# Pithy_Screen.net
KiCad netlist of a schematic drawn in EAGLE
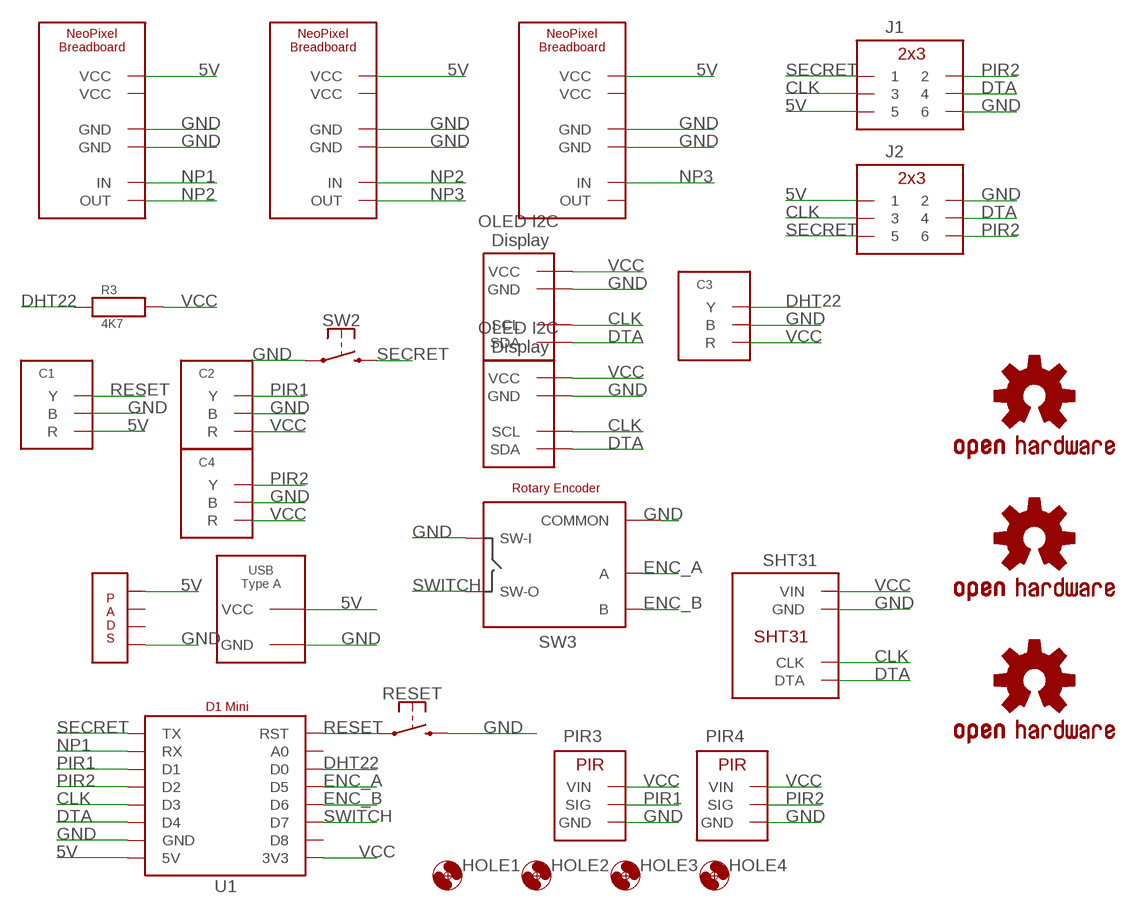
[diagram p0: schematic, sheet 1]

(export (version "E")
  (design (tool "Eeschema 10.0.6"))
  (components
    (comp (ref "C1")
      (value "JST_2MM_3PIN")
      (footprint "eagle-import:JST_2MM_3PIN")
      (libsource (lib "eagle-import") (part "JST_2MM_3PIN"))
    )
    (comp (ref "C2")
      (value "JST_2MM_3PIN")
      (footprint "eagle-import:JST_2MM_3PIN")
      (libsource (lib "eagle-import") (part "JST_2MM_3PIN"))
    )
    (comp (ref "C3")
      (value "JST_2MM_3PIN")
      (footprint "eagle-import:JST_2MM_3PIN")
      (libsource (lib "eagle-import") (part "JST_2MM_3PIN"))
    )
    (comp (ref "C4")
      (value "JST_2MM_3PIN")
      (footprint "eagle-import:JST_2MM_3PIN")
      (libsource (lib "eagle-import") (part "JST_2MM_3PIN"))
    )
    (comp (ref "HOLE1")
      (value "HOLE_3.2")
      (footprint "eagle-import:HOLE_3.2")
      (libsource (lib "eagle-import") (part "HOLE_3.2"))
    )
    (comp (ref "HOLE2")
      (value "HOLE_3.2")
      (footprint "eagle-import:HOLE_3.2")
      (libsource (lib "eagle-import") (part "HOLE_3.2"))
    )
    (comp (ref "HOLE3")
      (value "HOLE_3.2")
      (footprint "eagle-import:HOLE_3.2")
      (libsource (lib "eagle-import") (part "HOLE_3.2"))
    )
    (comp (ref "HOLE4")
      (value "HOLE_3.2")
      (footprint "eagle-import:HOLE_3.2")
      (libsource (lib "eagle-import") (part "HOLE_3.2"))
    )
    (comp (ref "J1")
      (value "DIL_2X03FEMALE")
      (footprint "eagle-import:2X3-RAF")
      (libsource (lib "eagle-import") (part "DIL_2X03FEMALE"))
    )
    (comp (ref "J2")
      (value "DIL_2X03FEMALE")
      (footprint "eagle-import:2X3-RAF")
      (libsource (lib "eagle-import") (part "DIL_2X03FEMALE"))
    )
    (comp (ref "LOGO1")
      (value "OSHW-LOGOL")
      (footprint "eagle-import:OSHW-LOGO-L")
      (libsource (lib "eagle-import") (part "OSHW-LOGOL"))
    )
    (comp (ref "LOGO2")
      (value "OSHW-LOGOM")
      (footprint "eagle-import:OSHW-LOGO-M")
      (libsource (lib "eagle-import") (part "OSHW-LOGOM"))
    )
    (comp (ref "LOGO3")
      (value "OSHW-LOGOS")
      (footprint "eagle-import:OSHW-LOGO-S")
      (libsource (lib "eagle-import") (part "OSHW-LOGOS"))
    )
    (comp (ref "NP1")
      (value "NEOPIXEL_BREADBOARD")
      (footprint "eagle-import:NEOPIXEL_BREADBOARD")
      (libsource (lib "eagle-import") (part "NEOPIXEL_BREADBOARD"))
    )
    (comp (ref "NP2")
      (value "NEOPIXEL_BREADBOARD")
      (footprint "eagle-import:NEOPIXEL_BREADBOARD")
      (libsource (lib "eagle-import") (part "NEOPIXEL_BREADBOARD"))
    )
    (comp (ref "NP3")
      (value "NEOPIXEL_BREADBOARD")
      (footprint "eagle-import:NEOPIXEL_BREADBOARD")
      (libsource (lib "eagle-import") (part "NEOPIXEL_BREADBOARD"))
    )
    (comp (ref "PIR3")
      (value "PIR45DEG")
      (footprint "eagle-import:PIR_45DEG")
      (libsource (lib "eagle-import") (part "PIR45DEG"))
    )
    (comp (ref "PIR4")
      (value "PIR45DEG")
      (footprint "eagle-import:PIR_45DEG")
      (libsource (lib "eagle-import") (part "PIR45DEG"))
    )
    (comp (ref "R3")
      (value "4K7")
      (footprint "eagle-import:1_4W_RESISTOR")
      (libsource (lib "eagle-import") (part "1/4W_RESISTOR"))
    )
    (comp (ref "RESET")
      (value "SPDT_MOMENTARY")
      (footprint "eagle-import:SPDT_RIGHT_ANGLE")
      (libsource (lib "eagle-import") (part "SPDT_MOMENTARY"))
    )
    (comp (ref "SHT31")
      (value "SHT31RIGHT_ANGLED")
      (footprint "eagle-import:SHT31_RIGHT_ANGLE")
      (libsource (lib "eagle-import") (part "SHT31RIGHT_ANGLED"))
    )
    (comp (ref "SW2")
      (value "SPDT_MOMENTARY")
      (footprint "eagle-import:SPDT_RIGHT_ANGLE")
      (libsource (lib "eagle-import") (part "SPDT_MOMENTARY"))
    )
    (comp (ref "SW3")
      (value "ENCODER")
      (footprint "eagle-import:ROTARY_ENCODER")
      (libsource (lib "eagle-import") (part "ROTARY_ENCODER"))
    )
    (comp (ref "U$1")
      (value "USB_TYPE_A")
      (footprint "eagle-import:USB_TYPE_A_BACKWARDS")
      (libsource (lib "eagle-import") (part "USB_TYPE_A"))
    )
    (comp (ref "U$2")
      (value "PADS_4")
      (footprint "eagle-import:PADS_4")
      (libsource (lib "eagle-import") (part "PADS_4"))
    )
    (comp (ref "U1")
      (value "D1_MINI")
      (footprint "eagle-import:D1_MINI")
      (libsource (lib "eagle-import") (part "D1_MINI"))
    )
    (comp (ref "U2")
      (value "OLED_I2C_0.9\"VCC_LEFT")
      (footprint "eagle-import:OLED_I2C_0.9__ALT")
      (libsource (lib "eagle-import") (part "OLED_I2C_0.9{dblquote}VCC_LEFT"))
    )
    (comp (ref "U3")
      (value "OLED_I2C_0.9\"VCC_LEFT")
      (footprint "eagle-import:OLED_I2C_0.9__ALT")
      (libsource (lib "eagle-import") (part "OLED_I2C_0.9{dblquote}VCC_LEFT"))
    )
  )
  (nets
    (net (code "1") (name "/5V") (class "Default")
      (node (ref "C1") (pin "RED") (pinfunction "R_RED") (pintype "bidirectional"))
      (node (ref "J1") (pin "5") (pinfunction "5_5") (pintype "bidirectional"))
      (node (ref "J2") (pin "1") (pinfunction "1_1") (pintype "bidirectional"))
      (node (ref "NP1") (pin "VCC") (pinfunction "VCC_VCC") (pintype "bidirectional"))
      (node (ref "NP2") (pin "VCC") (pinfunction "VCC_VCC") (pintype "bidirectional"))
      (node (ref "NP3") (pin "VCC") (pinfunction "VCC_VCC") (pintype "bidirectional"))
      (node (ref "U$1") (pin "VCC") (pinfunction "VCC_VCC") (pintype "bidirectional"))
      (node (ref "U$2") (pin "P$4") (pinfunction "P$4_P$4") (pintype "bidirectional"))
      (node (ref "U1") (pin "5V") (pinfunction "5V_5V") (pintype "bidirectional"))
    )
    (net (code "2") (name "/CLK") (class "Default")
      (node (ref "J1") (pin "3") (pinfunction "3_3") (pintype "bidirectional"))
      (node (ref "J2") (pin "3") (pinfunction "3_3") (pintype "bidirectional"))
      (node (ref "SHT31") (pin "CLK") (pinfunction "CLK_CLK") (pintype "bidirectional"))
      (node (ref "U1") (pin "D3") (pinfunction "D3_D3") (pintype "bidirectional"))
      (node (ref "U2") (pin "SCL") (pinfunction "SCL_SCL") (pintype "bidirectional"))
      (node (ref "U3") (pin "SCL") (pinfunction "SCL_SCL") (pintype "bidirectional"))
    )
    (net (code "3") (name "/DHT22") (class "Default")
      (node (ref "C3") (pin "YELLOW") (pinfunction "Y_YELLOW") (pintype "bidirectional"))
      (node (ref "R3") (pin "P$1") (pinfunction "P$1_P$1") (pintype "passive"))
      (node (ref "U1") (pin "D0") (pinfunction "D0_D0") (pintype "bidirectional"))
    )
    (net (code "4") (name "/DTA") (class "Default")
      (node (ref "J1") (pin "4") (pinfunction "4_4") (pintype "bidirectional"))
      (node (ref "J2") (pin "4") (pinfunction "4_4") (pintype "bidirectional"))
      (node (ref "SHT31") (pin "DTA") (pinfunction "DTA_DTA") (pintype "bidirectional"))
      (node (ref "U1") (pin "D4") (pinfunction "D4_D4") (pintype "bidirectional"))
      (node (ref "U2") (pin "SDA") (pinfunction "SDA_SDA") (pintype "bidirectional"))
      (node (ref "U3") (pin "SDA") (pinfunction "SDA_SDA") (pintype "bidirectional"))
    )
    (net (code "5") (name "/ENC_A") (class "Default")
      (node (ref "SW3") (pin "A") (pinfunction "A_A") (pintype "output"))
      (node (ref "U1") (pin "D5") (pinfunction "D5_D5") (pintype "bidirectional"))
    )
    (net (code "6") (name "/ENC_B") (class "Default")
      (node (ref "SW3") (pin "B") (pinfunction "B_B") (pintype "output"))
      (node (ref "U1") (pin "D6") (pinfunction "D6_D6") (pintype "bidirectional"))
    )
    (net (code "7") (name "/GND") (class "Default")
      (node (ref "C1") (pin "BLACK") (pinfunction "B_BLACK") (pintype "bidirectional"))
      (node (ref "C2") (pin "BLACK") (pinfunction "B_BLACK") (pintype "bidirectional"))
      (node (ref "C3") (pin "BLACK") (pinfunction "B_BLACK") (pintype "bidirectional"))
      (node (ref "C4") (pin "BLACK") (pinfunction "B_BLACK") (pintype "bidirectional"))
      (node (ref "J1") (pin "6") (pinfunction "6_6") (pintype "bidirectional"))
      (node (ref "J2") (pin "2") (pinfunction "2_2") (pintype "bidirectional"))
      (node (ref "NP1") (pin "GND") (pinfunction "GND_GND") (pintype "bidirectional"))
      (node (ref "NP1") (pin "GND@2") (pinfunction "GND_GND@2") (pintype "bidirectional"))
      (node (ref "NP2") (pin "GND") (pinfunction "GND_GND") (pintype "bidirectional"))
      (node (ref "NP2") (pin "GND@2") (pinfunction "GND_GND@2") (pintype "bidirectional"))
      (node (ref "NP3") (pin "GND") (pinfunction "GND_GND") (pintype "bidirectional"))
      (node (ref "NP3") (pin "GND@2") (pinfunction "GND_GND@2") (pintype "bidirectional"))
      (node (ref "PIR3") (pin "GND") (pinfunction "GND_GND") (pintype "bidirectional"))
      (node (ref "PIR4") (pin "GND") (pinfunction "GND_GND") (pintype "bidirectional"))
      (node (ref "RESET") (pin "2") (pinfunction "3_2") (pintype "passive"))
      (node (ref "SHT31") (pin "GND") (pinfunction "GND_GND") (pintype "bidirectional"))
      (node (ref "SW2") (pin "1") (pinfunction "1_1") (pintype "passive"))
      (node (ref "SW3") (pin "C") (pinfunction "COMMON_C") (pintype "input"))
      (node (ref "SW3") (pin "SW+") (pinfunction "SW-I_SW+") (pintype "input"))
      (node (ref "U$1") (pin "GND") (pinfunction "GND_GND") (pintype "bidirectional"))
      (node (ref "U$2") (pin "P$1") (pinfunction "P$1_P$1") (pintype "bidirectional"))
      (node (ref "U1") (pin "GND") (pinfunction "GND_GND") (pintype "bidirectional"))
      (node (ref "U2") (pin "GND") (pinfunction "GND_GND") (pintype "power_in"))
      (node (ref "U3") (pin "GND") (pinfunction "GND_GND") (pintype "power_in"))
    )
    (net (code "8") (name "/NP1") (class "Default")
      (node (ref "NP1") (pin "IN") (pinfunction "IN_IN") (pintype "bidirectional"))
      (node (ref "U1") (pin "RX") (pinfunction "RX_RX") (pintype "bidirectional"))
    )
    (net (code "9") (name "/NP2") (class "Default")
      (node (ref "NP1") (pin "OUT") (pinfunction "OUT_OUT") (pintype "bidirectional"))
      (node (ref "NP2") (pin "IN") (pinfunction "IN_IN") (pintype "bidirectional"))
    )
    (net (code "10") (name "/NP3") (class "Default")
      (node (ref "NP2") (pin "OUT") (pinfunction "OUT_OUT") (pintype "bidirectional"))
      (node (ref "NP3") (pin "IN") (pinfunction "IN_IN") (pintype "bidirectional"))
    )
    (net (code "11") (name "/PIR1") (class "Default")
      (node (ref "C2") (pin "YELLOW") (pinfunction "Y_YELLOW") (pintype "bidirectional"))
      (node (ref "PIR3") (pin "SIG") (pinfunction "SIG_SIG") (pintype "bidirectional"))
      (node (ref "U1") (pin "D1") (pinfunction "D1_D1") (pintype "bidirectional"))
    )
    (net (code "12") (name "/PIR2") (class "Default")
      (node (ref "C4") (pin "YELLOW") (pinfunction "Y_YELLOW") (pintype "bidirectional"))
      (node (ref "J1") (pin "2") (pinfunction "2_2") (pintype "bidirectional"))
      (node (ref "J2") (pin "6") (pinfunction "6_6") (pintype "bidirectional"))
      (node (ref "PIR4") (pin "SIG") (pinfunction "SIG_SIG") (pintype "bidirectional"))
      (node (ref "U1") (pin "D2") (pinfunction "D2_D2") (pintype "bidirectional"))
    )
    (net (code "13") (name "/RESET") (class "Default")
      (node (ref "C1") (pin "YELLOW") (pinfunction "Y_YELLOW") (pintype "bidirectional"))
      (node (ref "RESET") (pin "1") (pinfunction "1_1") (pintype "passive"))
      (node (ref "U1") (pin "RST") (pinfunction "RST_RST") (pintype "bidirectional"))
    )
    (net (code "14") (name "/SECRET") (class "Default")
      (node (ref "J1") (pin "1") (pinfunction "1_1") (pintype "bidirectional"))
      (node (ref "J2") (pin "5") (pinfunction "5_5") (pintype "bidirectional"))
      (node (ref "SW2") (pin "2") (pinfunction "3_2") (pintype "passive"))
      (node (ref "U1") (pin "TX") (pinfunction "TX_TX") (pintype "bidirectional"))
    )
    (net (code "15") (name "/SWITCH") (class "Default")
      (node (ref "SW3") (pin "SW-") (pinfunction "SW-O_SW-") (pintype "output"))
      (node (ref "U1") (pin "D7") (pinfunction "D7_D7") (pintype "bidirectional"))
    )
    (net (code "16") (name "/VCC") (class "Default")
      (node (ref "C2") (pin "RED") (pinfunction "R_RED") (pintype "bidirectional"))
      (node (ref "C3") (pin "RED") (pinfunction "R_RED") (pintype "bidirectional"))
      (node (ref "C4") (pin "RED") (pinfunction "R_RED") (pintype "bidirectional"))
      (node (ref "PIR3") (pin "VCC") (pinfunction "VIN_VCC") (pintype "bidirectional"))
      (node (ref "PIR4") (pin "VCC") (pinfunction "VIN_VCC") (pintype "bidirectional"))
      (node (ref "R3") (pin "P$2") (pinfunction "P$2_P$2") (pintype "passive"))
      (node (ref "SHT31") (pin "VIN") (pinfunction "VIN_VIN") (pintype "bidirectional"))
      (node (ref "U1") (pin "3V3") (pinfunction "3V3_3V3") (pintype "bidirectional"))
      (node (ref "U2") (pin "VCC") (pinfunction "VCC_VCC") (pintype "power_in"))
      (node (ref "U3") (pin "VCC") (pinfunction "VCC_VCC") (pintype "power_in"))
    )
    (net (code "17") (name "unconnected-(NP1-VCC-PadVCC@2)") (class "Default")
      (node (ref "NP1") (pin "VCC@2") (pinfunction "VCC_VCC@2") (pintype "bidirectional"))
    )
    (net (code "18") (name "unconnected-(NP2-VCC-PadVCC@2)") (class "Default")
      (node (ref "NP2") (pin "VCC@2") (pinfunction "VCC_VCC@2") (pintype "bidirectional"))
    )
    (net (code "19") (name "unconnected-(NP3-PadOUT)") (class "Default")
      (node (ref "NP3") (pin "OUT") (pinfunction "OUT_OUT") (pintype "bidirectional"))
    )
    (net (code "20") (name "unconnected-(NP3-VCC-PadVCC@2)") (class "Default")
      (node (ref "NP3") (pin "VCC@2") (pinfunction "VCC_VCC@2") (pintype "bidirectional"))
    )
    (net (code "21") (name "unconnected-(U$2-PadP$2)") (class "Default")
      (node (ref "U$2") (pin "P$2") (pinfunction "P$2_P$2") (pintype "bidirectional"))
    )
    (net (code "22") (name "unconnected-(U$2-PadP$3)") (class "Default")
      (node (ref "U$2") (pin "P$3") (pinfunction "P$3_P$3") (pintype "bidirectional"))
    )
    (net (code "23") (name "unconnected-(U1-PadA0)") (class "Default")
      (node (ref "U1") (pin "A0") (pinfunction "A0_A0") (pintype "bidirectional"))
    )
    (net (code "24") (name "unconnected-(U1-PadD8)") (class "Default")
      (node (ref "U1") (pin "D8") (pinfunction "D8_D8") (pintype "bidirectional"))
    )
  )
)
